# 1_Power.net
KiCad netlist of a schematic drawn in Altium Designer
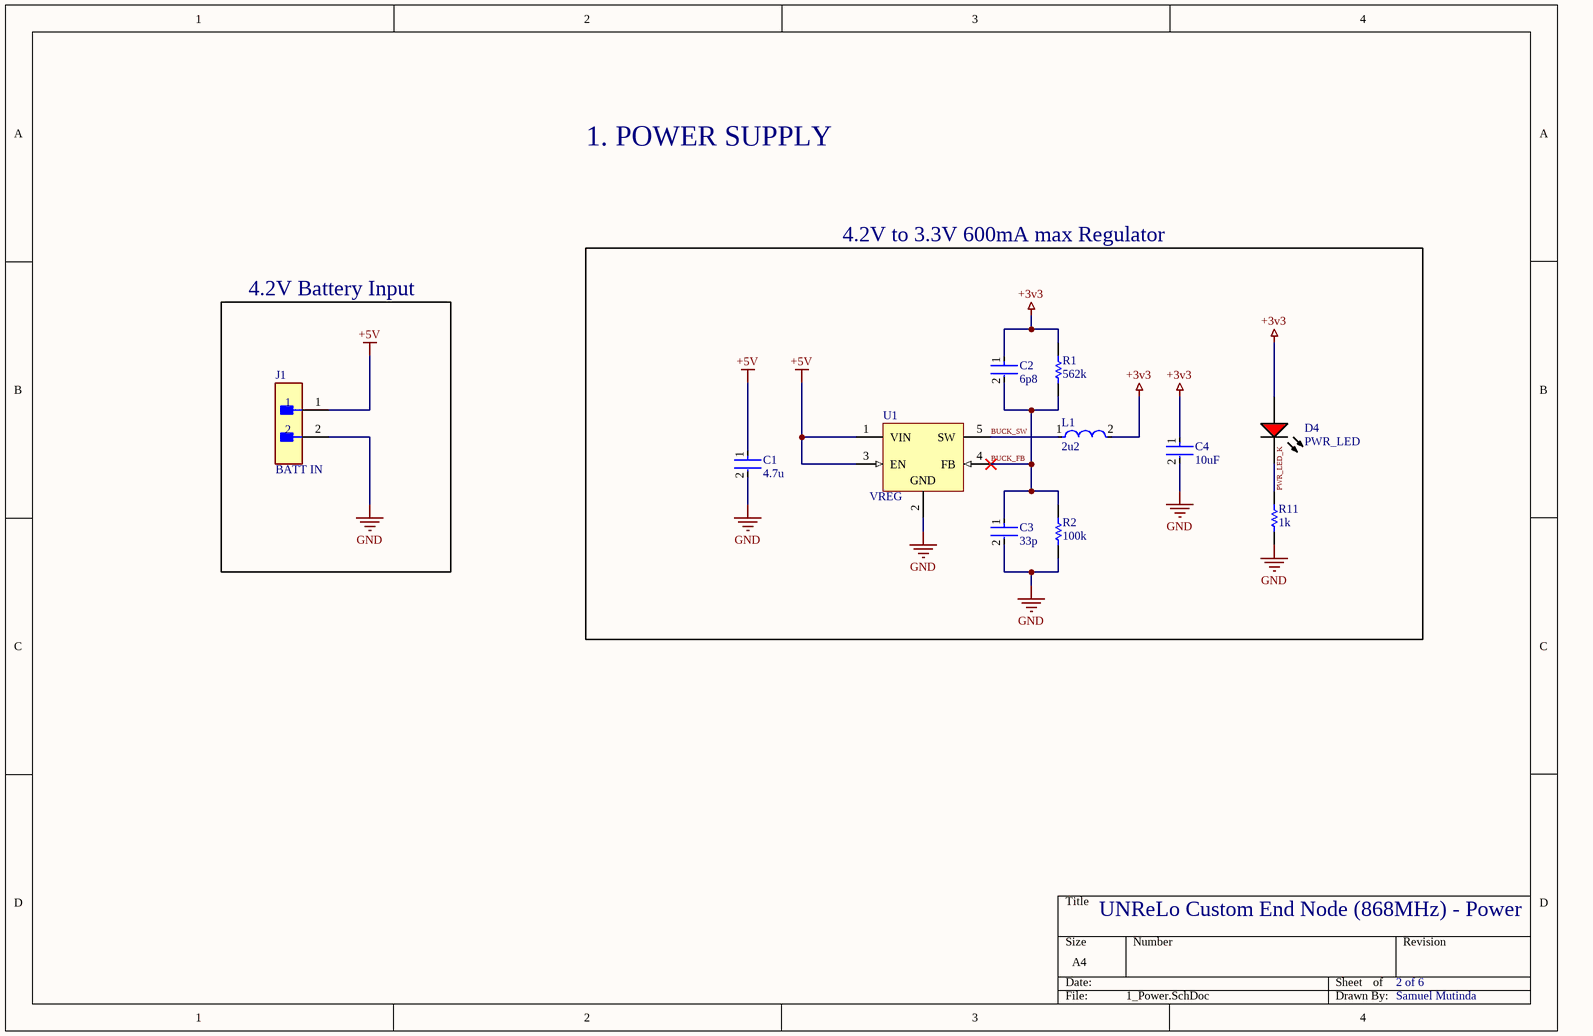
[diagram p0: 1_Power.SchDoc]

(export (version "E")
  (design (tool "Eeschema 10.0.6"))
  (components
    (comp (ref "C1")
      (value "4.7u")
      (footprint "FP-GRM155-0_1-IPC_B")
      (description "Chip Multilayer Ceramic Capacitors for General Purpose, 0402, 4.7uF, X5R, 15%, 20%, 6.3V")
      (fields (field (name "VOLTAGE") "6.3V") (field (name "TOLERANCE") "20%"))
      (libsource (lib "Altium Content Vault") (part "11868f565c42a9108669ba33697ecf6"))
    )
    (comp (ref "C2")
      (value "6p8")
      (footprint "FP-C0603C-CF-MFG")
      (description "CAP CER 6.8PF 50V NP0 0603")
      (fields
        (field (name "MANUFACTURER PART NUMBER") "C0603C689C5GACTU")
        (field (name "OCTOPART") "https://octopart.com/c0603c689c5gactu-kemet-8718591")
      )
      (libsource (lib "Altium Content Vault") (part "b4654b650e69147ec39a6b967a45e02"))
    )
    (comp (ref "C3")
      (value "33p")
      (footprint "FP-CC0603-0_9-IPC_C")
      (description "CAP CER 33PF 50V C0G/NPO 0603")
      (fields (field (name "TOLERANCE") "5%") (field (name "VOLTAGE") "50V"))
      (libsource (lib "Altium Content Vault") (part "b4654b650e69147ec39a6b967a45e02"))
    )
    (comp (ref "C4")
      (value "10uF")
      (footprint "FP-GRM188-0_1-e0_2_0_55-IPC_A")
      (description "10 µF ±10% 10V Ceramic Capacitor X5R 0603 (1608 Metric)")
      (fields (field (name "VOLTAGE") "6.3V") (field (name "TOLERANCE") "20%"))
      (libsource (lib "Altium Content Vault") (part "02cd4be3c70576c341d710602a673aa"))
    )
    (comp (ref "D4")
      (value "PWR_LED")
      (footprint "VISH-TLMS1000_V")
      (description "Low Current LED, 40 mW, 1.8 V, -40 to 100 degC, 2-Pin SMD (0603), RoHS, Tape and Reel")
      (fields (field (name "JLCPCB PART #") "C2286") (field (name "MANUFACTURER") "Vishay"))
      (libsource (lib "Altium Content Vault") (part "LED-RED-AK-2"))
    )
    (comp (ref "J1")
      (value "BATT IN")
      (footprint "FP-53254-0270-MFG")
      (description "CONN HEADER R/A 2POS 2MM")
      (libsource (lib "Altium Content Vault") (part "3bc925449376181038e59eaffc5286c"))
    )
    (comp (ref "L1")
      (value "2u2")
      (footprint "FP-LQM21PH_G0-IPC_C")
      (description "2.2 µH Unshielded Multilayer Inductor 900 mA 170mOhm Max 0806 (2016 Metric)")
      (fields (field (name "TOLERANCE") "30%"))
      (libsource (lib "Altium Content Vault") (part "725321dda6339637d4d059423bc1c3c"))
    )
    (comp (ref "R1")
      (value "562k")
      (footprint "RESC1609X50X30NL10T20")
      (libsource (lib "Altium Content Vault") (part "RES"))
    )
    (comp (ref "R2")
      (value "100k")
      (footprint "RESC1608X55X30ML20T20")
      (description "100 kOhms ±0.1% 0.1W, 1/10W Chip Resistor 0603 (1608 Metric) Automotive AEC-Q200 Thin Film")
      (libsource (lib "Altium Content Vault") (part "RES"))
    )
    (comp (ref "R11")
      (value "1k")
      (footprint "RESC1005X40X25NL05T05")
      (description "Chip Resistor, 1 KOhm, +/- 1%, 100 mW, -55 to 155 degC, 0402 (1005 Metric), RoHS, Tape and Reel")
      (fields (field (name "TOLERANCE") "1%"))
      (libsource (lib "Altium Content Vault") (part "RES-2"))
    )
    (comp (ref "U1")
      (value "VREG")
      (footprint "DBV0005A_L")
      (description "2MHz, 600mA Step-Down DC-DC Converter, 5-pin SOT-23, Pb-Free")
      (fields (field (name "MANUFACTURER") "Texas Instruments"))
      (libsource (lib "Altium Content Vault") (part "PM-DCDC-LM3670-5"))
    )
  )
  (nets
    (net (code "1") (name "+3v3") (class "Default")
      (node (ref "C2") (pin "1") (pinfunction "1_1") (pintype "passive"))
      (node (ref "C4") (pin "1") (pinfunction "1_1") (pintype "passive"))
      (node (ref "D4") (pin "1") (pinfunction "A_1") (pintype "passive"))
      (node (ref "L1") (pin "2") (pinfunction "2_2") (pintype "passive"))
      (node (ref "R1") (pin "2") (pinfunction "2_2") (pintype "passive"))
    )
    (net (code "2") (name "+5V") (class "Default")
      (node (ref "C1") (pin "1") (pinfunction "1_1") (pintype "passive"))
      (node (ref "J1") (pin "1") (pinfunction "1_1") (pintype "passive"))
      (node (ref "U1") (pin "1") (pinfunction "VIN_1") (pintype "power_in"))
      (node (ref "U1") (pin "3") (pinfunction "EN_3") (pintype "input"))
    )
    (net (code "3") (name "/BUCK_FB") (class "Default")
      (node (ref "C2") (pin "2") (pinfunction "2_2") (pintype "passive"))
      (node (ref "C3") (pin "1") (pinfunction "1_1") (pintype "passive"))
      (node (ref "R1") (pin "1") (pinfunction "1_1") (pintype "passive"))
      (node (ref "R2") (pin "2") (pinfunction "2_2") (pintype "passive"))
      (node (ref "U1") (pin "4") (pinfunction "FB_4") (pintype "input"))
    )
    (net (code "4") (name "/BUCK_SW") (class "Default")
      (node (ref "L1") (pin "1") (pinfunction "1_1") (pintype "passive"))
      (node (ref "U1") (pin "5") (pinfunction "SW_5") (pintype "power_in"))
    )
    (net (code "5") (name "/PWR_LED_K") (class "Default")
      (node (ref "D4") (pin "2") (pinfunction "K_2") (pintype "passive"))
      (node (ref "R11") (pin "2") (pinfunction "2_2") (pintype "passive"))
    )
    (net (code "6") (name "GND") (class "Default")
      (node (ref "C1") (pin "2") (pinfunction "2_2") (pintype "passive"))
      (node (ref "C3") (pin "2") (pinfunction "2_2") (pintype "passive"))
      (node (ref "C4") (pin "2") (pinfunction "2_2") (pintype "passive"))
      (node (ref "J1") (pin "2") (pinfunction "2_2") (pintype "passive"))
      (node (ref "R11") (pin "1") (pinfunction "1_1") (pintype "passive"))
      (node (ref "R2") (pin "1") (pinfunction "1_1") (pintype "passive"))
      (node (ref "U1") (pin "2") (pinfunction "GND_2") (pintype "power_in"))
    )
  )
)
